# ADC.net
KiCad netlist of a schematic drawn in Altium Designer
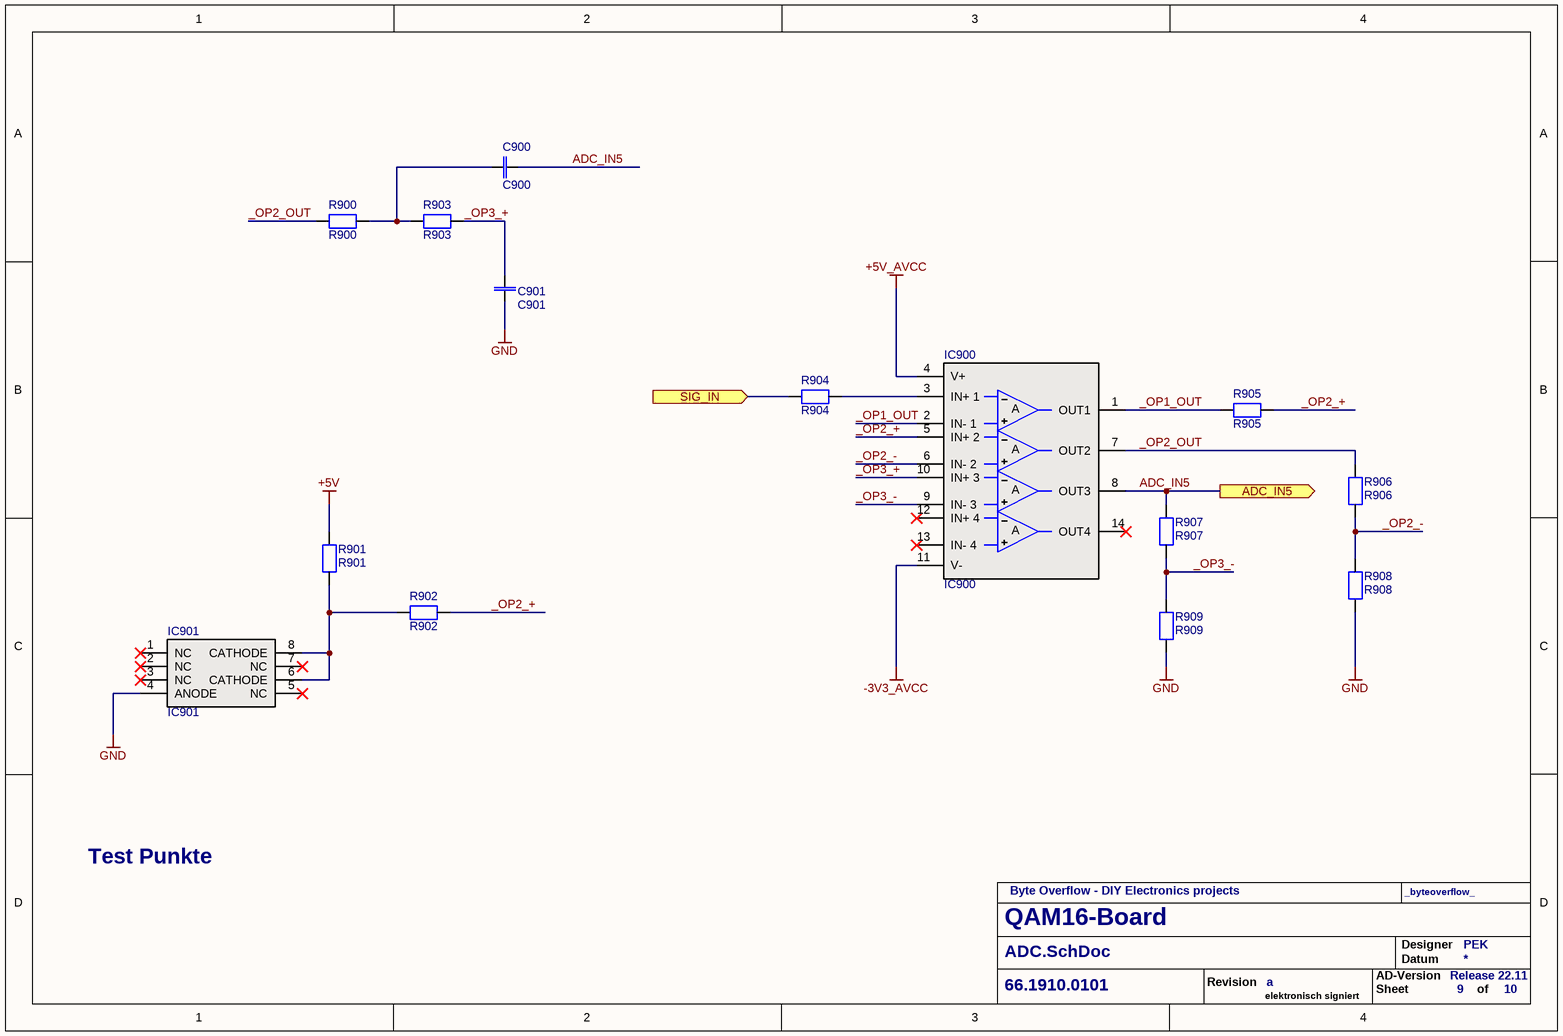
[diagram p0: ADC.SchDoc]

(export (version "E")
  (design (tool "Eeschema 10.0.6"))
  (components
    (comp (ref "C900")
      (value "C 220nF 16V")
      (footprint "0603-1608")
      (description "Capacitor")
      (fields
        (field (name "MANUFACTURER") "KEMET")
        (field (name "MANUFACTURER PART NUMBER") "C0603C224K4RAC7867")
        (field (name "VERIFICATION") "05.07.2012 OPT")
      )
      (libsource (lib "Database_Libs1") (part "Kondensator"))
    )
    (comp (ref "C901")
      (value "C 220nF 16V")
      (footprint "0603-1608")
      (description "Capacitor")
      (fields
        (field (name "MANUFACTURER") "KEMET")
        (field (name "MANUFACTURER PART NUMBER") "C0603C224K4RAC7867")
        (field (name "VERIFICATION") "05.07.2012 OPT")
      )
      (libsource (lib "Database_Libs1") (part "Kondensator"))
    )
    (comp (ref "IC900")
      (value "LMC6484IMX/NOPB")
      (footprint "SOIC-14")
      (description "OPAMP")
      (fields (field (name "MANUFACTURER") "Texas Instruments"))
      (libsource (lib "Database_Libs1") (part "LMC6484"))
    )
    (comp (ref "IC901")
      (value "LT1004IPWR-1-2")
      (footprint "MO-153AA")
      (description "Voltage reference")
      (fields (field (name "MANUFACTURER") "Texas Instruments"))
      (libsource (lib "Database_Libs1") (part "LT1004IPWR"))
    )
    (comp (ref "R900")
      (value "R 10k 1%")
      (footprint "0603-1608")
      (description "Resistor")
      (fields
        (field (name "MANUFACTURER") "Vishay Dale")
        (field (name "MANUFACTURER PART NUMBER") "CRCW060310K0FKEAHP")
        (field (name "VERIFICATION") "05.07.2012 OPT")
      )
      (libsource (lib "Database_Libs1") (part "Resistor"))
    )
    (comp (ref "R901")
      (value "R 100k 1.0%")
      (footprint "0805-2012")
      (description "Resistor")
      (fields
        (field (name "MANUFACTURER") "Vishay Dale")
        (field (name "MANUFACTURER PART NUMBER") "CRCW0805100KFKEA")
      )
      (libsource (lib "Database_Libs1") (part "Resistor"))
    )
    (comp (ref "R902")
      (value "R 10k 1%")
      (footprint "0603-1608")
      (description "Resistor")
      (fields
        (field (name "MANUFACTURER") "Vishay Dale")
        (field (name "MANUFACTURER PART NUMBER") "CRCW060310K0FKEAHP")
        (field (name "VERIFICATION") "05.07.2012 OPT")
      )
      (libsource (lib "Database_Libs1") (part "Resistor"))
    )
    (comp (ref "R903")
      (value "R 10k 1%")
      (footprint "0603-1608")
      (description "Resistor")
      (fields
        (field (name "MANUFACTURER") "Vishay Dale")
        (field (name "MANUFACTURER PART NUMBER") "CRCW060310K0FKEAHP")
        (field (name "VERIFICATION") "05.07.2012 OPT")
      )
      (libsource (lib "Database_Libs1") (part "Resistor"))
    )
    (comp (ref "R904")
      (value "R 10k 1%")
      (footprint "0603-1608")
      (description "Resistor")
      (fields
        (field (name "MANUFACTURER") "Vishay Dale")
        (field (name "MANUFACTURER PART NUMBER") "CRCW060310K0FKEAHP")
        (field (name "VERIFICATION") "05.07.2012 OPT")
      )
      (libsource (lib "Database_Libs1") (part "Resistor"))
    )
    (comp (ref "R905")
      (value "R 10k 1%")
      (footprint "0603-1608")
      (description "Resistor")
      (fields
        (field (name "MANUFACTURER") "Vishay Dale")
        (field (name "MANUFACTURER PART NUMBER") "CRCW060310K0FKEAHP")
        (field (name "VERIFICATION") "05.07.2012 OPT")
      )
      (libsource (lib "Database_Libs1") (part "Resistor"))
    )
    (comp (ref "R906")
      (value "R 6.8k 1%")
      (footprint "0603-1608")
      (description "Resistor")
      (fields
        (field (name "MANUFACTURER") "Vishay Dale")
        (field (name "MANUFACTURER PART NUMBER") "CRCW06036K80FKEA")
        (field (name "VERIFICATION") "05.07.2012 OPT")
      )
      (libsource (lib "Database_Libs1") (part "Resistor"))
    )
    (comp (ref "R907")
      (value "R 6.8k 1%")
      (footprint "0603-1608")
      (description "Resistor")
      (fields
        (field (name "MANUFACTURER") "Vishay Dale")
        (field (name "MANUFACTURER PART NUMBER") "CRCW06036K80FKEA")
        (field (name "VERIFICATION") "05.07.2012 OPT")
      )
      (libsource (lib "Database_Libs1") (part "Resistor"))
    )
    (comp (ref "R908")
      (value "R 10k 1%")
      (footprint "0603-1608")
      (description "Resistor")
      (fields
        (field (name "MANUFACTURER") "Vishay Dale")
        (field (name "MANUFACTURER PART NUMBER") "CRCW060310K0FKEAHP")
        (field (name "VERIFICATION") "05.07.2012 OPT")
      )
      (libsource (lib "Database_Libs1") (part "Resistor"))
    )
    (comp (ref "R909")
      (value "R 10k 1%")
      (footprint "0603-1608")
      (description "Resistor")
      (fields
        (field (name "MANUFACTURER") "Vishay Dale")
        (field (name "MANUFACTURER PART NUMBER") "CRCW060310K0FKEAHP")
        (field (name "VERIFICATION") "05.07.2012 OPT")
      )
      (libsource (lib "Database_Libs1") (part "Resistor"))
    )
  )
  (nets
    (net (code "1") (name "+5V") (class "Default")
      (node (ref "R901") (pin "1") (pinfunction "1_1") (pintype "passive"))
    )
    (net (code "2") (name "+5V_AVCC") (class "Default")
      (node (ref "IC900") (pin "4") (pinfunction "V+_4") (pintype "passive"))
    )
    (net (code "3") (name "-3V3_AVCC") (class "Default")
      (node (ref "IC900") (pin "11") (pinfunction "V-_11") (pintype "passive"))
    )
    (net (code "4") (name "/ADC_IN5") (class "Default")
      (node (ref "C900") (pin "2") (pinfunction "2_2") (pintype "passive"))
      (node (ref "IC900") (pin "8") (pinfunction "OUT3_8") (pintype "passive"))
      (node (ref "R907") (pin "1") (pinfunction "1_1") (pintype "passive"))
    )
    (net (code "5") (name "/SIG_IN") (class "Default")
      (node (ref "R904") (pin "1") (pinfunction "1_1") (pintype "passive"))
    )
    (net (code "6") (name "/_OP1_OUT") (class "Default")
      (node (ref "IC900") (pin "1") (pinfunction "OUT1_1") (pintype "passive"))
      (node (ref "IC900") (pin "2") (pinfunction "IN-_1_2") (pintype "passive"))
      (node (ref "R905") (pin "1") (pinfunction "1_1") (pintype "passive"))
    )
    (net (code "7") (name "/_OP2_+") (class "Default")
      (node (ref "IC900") (pin "5") (pinfunction "IN+_2_5") (pintype "passive"))
      (node (ref "R902") (pin "2") (pinfunction "2_2") (pintype "passive"))
      (node (ref "R905") (pin "2") (pinfunction "2_2") (pintype "passive"))
    )
    (net (code "8") (name "/_OP2_-") (class "Default")
      (node (ref "IC900") (pin "6") (pinfunction "IN-_2_6") (pintype "passive"))
      (node (ref "R906") (pin "2") (pinfunction "2_2") (pintype "passive"))
      (node (ref "R908") (pin "2") (pinfunction "2_2") (pintype "passive"))
    )
    (net (code "9") (name "/_OP2_OUT") (class "Default")
      (node (ref "IC900") (pin "7") (pinfunction "OUT2_7") (pintype "passive"))
      (node (ref "R900") (pin "1") (pinfunction "1_1") (pintype "passive"))
      (node (ref "R906") (pin "1") (pinfunction "1_1") (pintype "passive"))
    )
    (net (code "10") (name "/_OP3_+") (class "Default")
      (node (ref "C901") (pin "2") (pinfunction "2_2") (pintype "passive"))
      (node (ref "IC900") (pin "10") (pinfunction "IN+_3_10") (pintype "passive"))
      (node (ref "R903") (pin "2") (pinfunction "2_2") (pintype "passive"))
    )
    (net (code "11") (name "/_OP3_-") (class "Default")
      (node (ref "IC900") (pin "9") (pinfunction "IN-_3_9") (pintype "passive"))
      (node (ref "R907") (pin "2") (pinfunction "2_2") (pintype "passive"))
      (node (ref "R909") (pin "2") (pinfunction "2_2") (pintype "passive"))
    )
    (net (code "12") (name "GND") (class "Default")
      (node (ref "C901") (pin "1") (pinfunction "1_1") (pintype "passive"))
      (node (ref "IC901") (pin "4") (pinfunction "ANODE_4") (pintype "passive"))
      (node (ref "R908") (pin "1") (pinfunction "1_1") (pintype "passive"))
      (node (ref "R909") (pin "1") (pinfunction "1_1") (pintype "passive"))
    )
    (net (code "13") (name "Net-(C900-Pad1)") (class "Default")
      (node (ref "C900") (pin "1") (pinfunction "1_1") (pintype "passive"))
      (node (ref "R900") (pin "2") (pinfunction "2_2") (pintype "passive"))
      (node (ref "R903") (pin "1") (pinfunction "1_1") (pintype "passive"))
    )
    (net (code "14") (name "Net-(IC900-IN+_1)") (class "Default")
      (node (ref "IC900") (pin "3") (pinfunction "IN+_1_3") (pintype "passive"))
      (node (ref "R904") (pin "2") (pinfunction "2_2") (pintype "passive"))
    )
    (net (code "15") (name "Net-(IC901-CATHODE-Pad6)") (class "Default")
      (node (ref "IC901") (pin "6") (pinfunction "CATHODE_6") (pintype "passive"))
      (node (ref "IC901") (pin "8") (pinfunction "CATHODE_8") (pintype "passive"))
      (node (ref "R901") (pin "2") (pinfunction "2_2") (pintype "passive"))
      (node (ref "R902") (pin "1") (pinfunction "1_1") (pintype "passive"))
    )
    (net (code "16") (name "unconnected-(IC900-IN+_4-Pad12)") (class "Default")
      (node (ref "IC900") (pin "12") (pinfunction "IN+_4_12") (pintype "passive+no_connect"))
    )
    (net (code "17") (name "unconnected-(IC900-IN-_4-Pad13)") (class "Default")
      (node (ref "IC900") (pin "13") (pinfunction "IN-_4_13") (pintype "passive+no_connect"))
    )
    (net (code "18") (name "unconnected-(IC900-OUT4-Pad14)") (class "Default")
      (node (ref "IC900") (pin "14") (pinfunction "OUT4_14") (pintype "passive+no_connect"))
    )
    (net (code "19") (name "unconnected-(IC901-NC-Pad1)") (class "Default")
      (node (ref "IC901") (pin "1") (pinfunction "NC_1") (pintype "passive+no_connect"))
    )
    (net (code "20") (name "unconnected-(IC901-NC-Pad2)") (class "Default")
      (node (ref "IC901") (pin "2") (pinfunction "NC_2") (pintype "passive+no_connect"))
    )
    (net (code "21") (name "unconnected-(IC901-NC-Pad3)") (class "Default")
      (node (ref "IC901") (pin "3") (pinfunction "NC_3") (pintype "passive+no_connect"))
    )
    (net (code "22") (name "unconnected-(IC901-NC-Pad5)") (class "Default")
      (node (ref "IC901") (pin "5") (pinfunction "NC_5") (pintype "passive+no_connect"))
    )
    (net (code "23") (name "unconnected-(IC901-NC-Pad7)") (class "Default")
      (node (ref "IC901") (pin "7") (pinfunction "NC_7") (pintype "passive+no_connect"))
    )
  )
)
